# main_low_pass.net
KiCad netlist of a schematic drawn in EAGLE
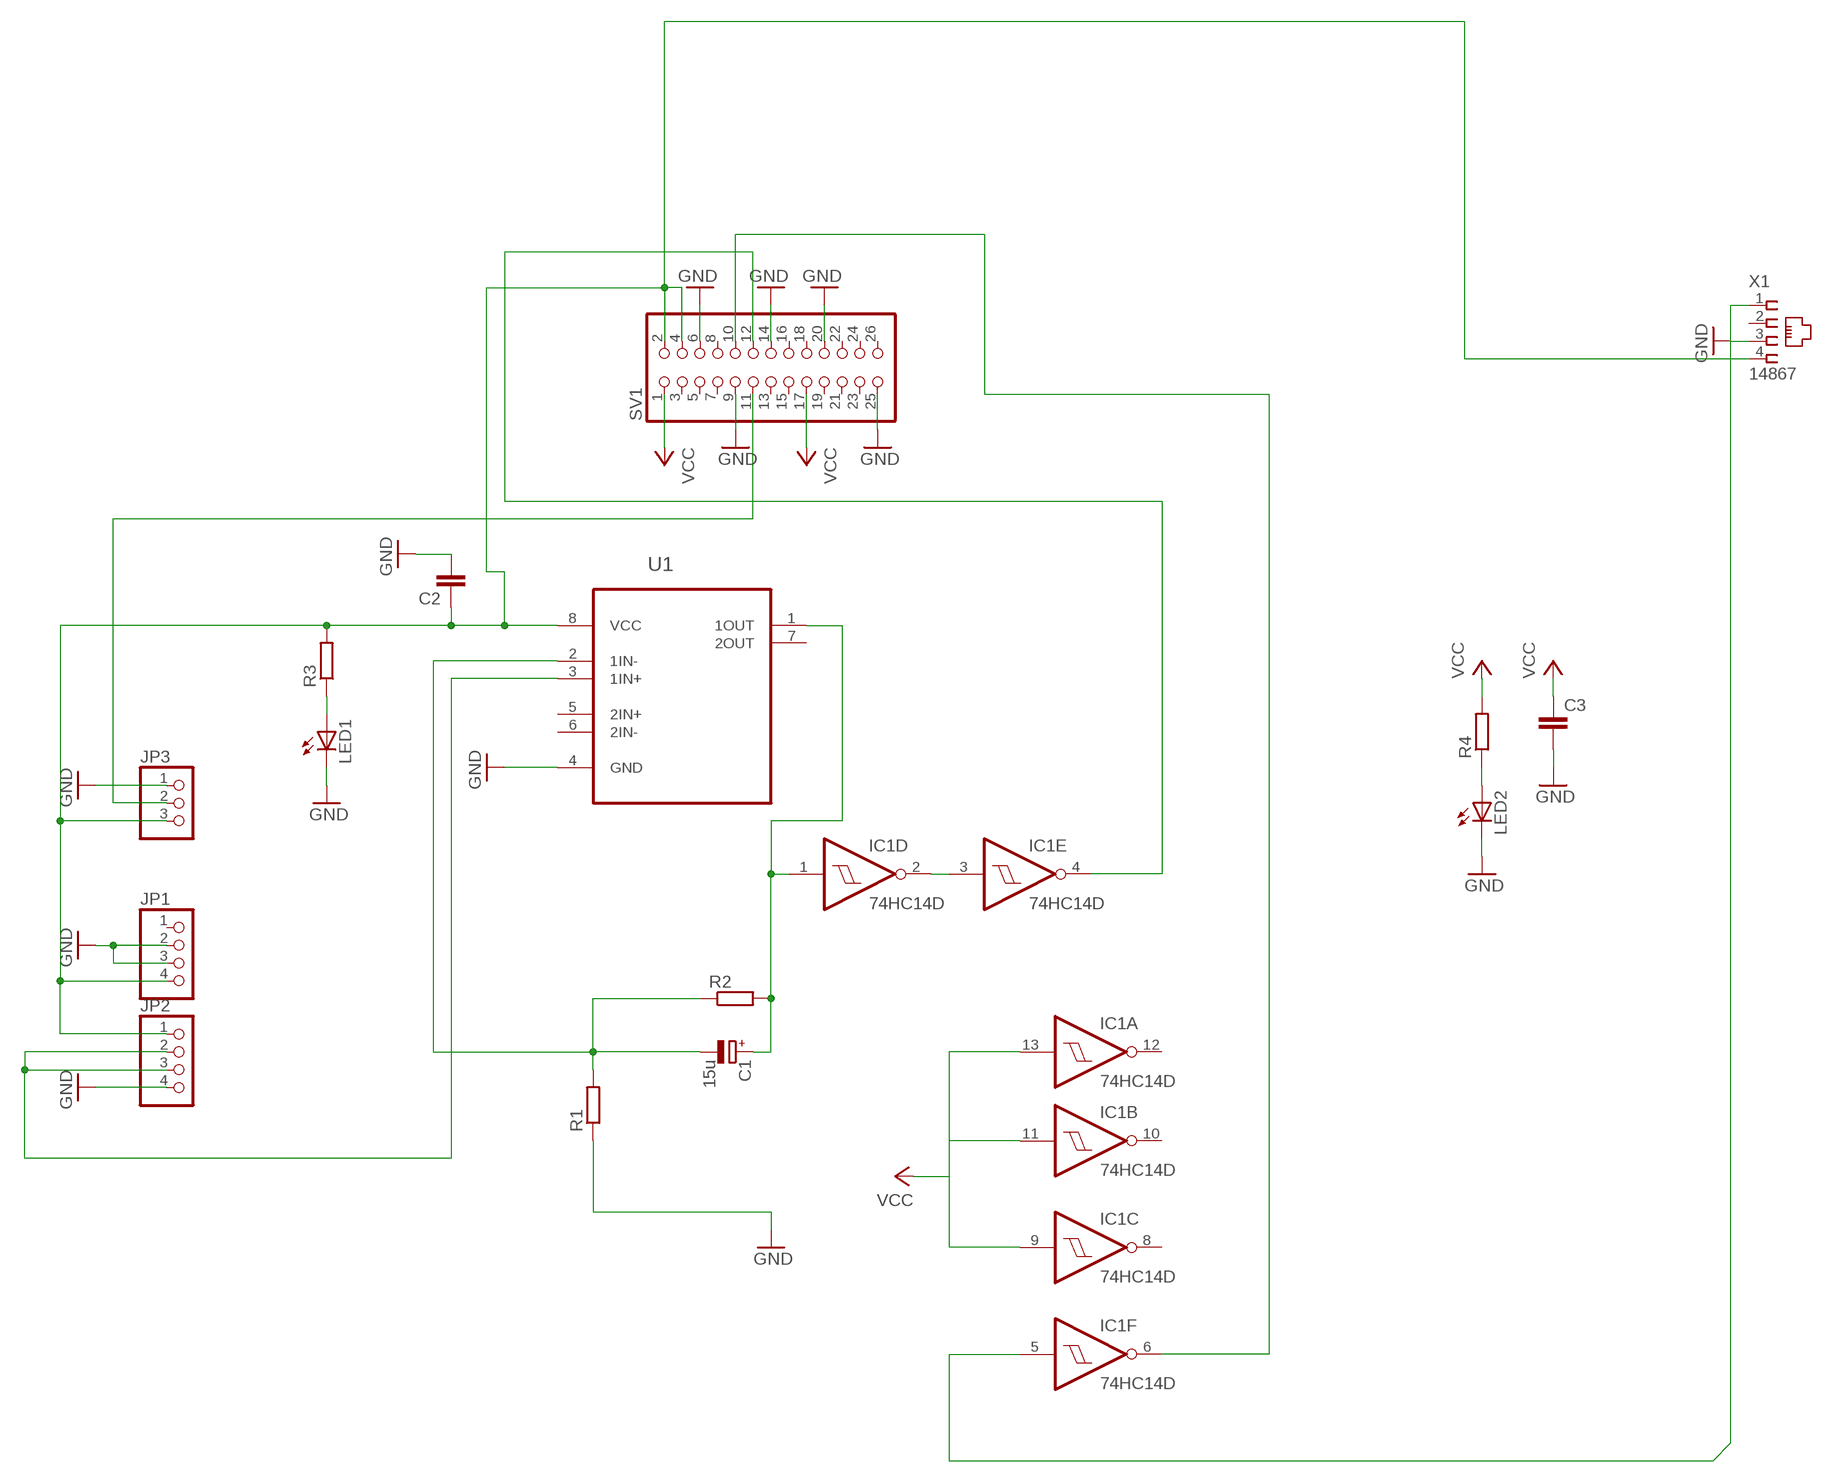
[diagram p0: schematic, sheet 1]

(export (version "E")
  (design (tool "Eeschema 10.0.6"))
  (components
    (comp (ref "C1")
      (value "15u")
      (footprint "eagle-import:153CLV-0605")
      (libsource (lib "eagle-import") (part "CPOL-EU153CLV-0605"))
    )
    (comp (ref "C2")
      (value "C-EUC0805")
      (footprint "eagle-import:C0805")
      (libsource (lib "eagle-import") (part "C-EUC0805"))
    )
    (comp (ref "C3")
      (value "C-EUC0805")
      (footprint "eagle-import:C0805")
      (libsource (lib "eagle-import") (part "C-EUC0805"))
    )
    (comp (ref "IC1")
      (value "74HC14D")
      (footprint "eagle-import:SO14")
      (libsource (lib "eagle-import") (part "7414DHC"))
    )
    (comp (ref "JP1")
      (value "PINHD-1X4")
      (footprint "eagle-import:1X04")
      (libsource (lib "eagle-import") (part "PINHD-1X4"))
    )
    (comp (ref "JP2")
      (value "PINHD-1X4")
      (footprint "eagle-import:1X04")
      (libsource (lib "eagle-import") (part "PINHD-1X4"))
    )
    (comp (ref "JP3")
      (value "PINHD-1X3")
      (footprint "eagle-import:1X03")
      (libsource (lib "eagle-import") (part "PINHD-1X3"))
    )
    (comp (ref "LED1")
      (value "LEDCHIP-LED0805")
      (footprint "eagle-import:CHIP-LED0805")
      (libsource (lib "eagle-import") (part "LEDCHIP-LED0805"))
    )
    (comp (ref "LED2")
      (value "LEDCHIP-LED0805")
      (footprint "eagle-import:CHIP-LED0805")
      (libsource (lib "eagle-import") (part "LEDCHIP-LED0805"))
    )
    (comp (ref "R1")
      (value "R-EU_R0805")
      (footprint "eagle-import:R0805")
      (libsource (lib "eagle-import") (part "R-EU_R0805"))
    )
    (comp (ref "R2")
      (value "R-EU_R0805")
      (footprint "eagle-import:R0805")
      (libsource (lib "eagle-import") (part "R-EU_R0805"))
    )
    (comp (ref "R3")
      (value "R-EU_R0805")
      (footprint "eagle-import:R0805")
      (libsource (lib "eagle-import") (part "R-EU_R0805"))
    )
    (comp (ref "R4")
      (value "R-EU_R0805")
      (footprint "eagle-import:R0805")
      (libsource (lib "eagle-import") (part "R-EU_R0805"))
    )
    (comp (ref "SV1")
      (value "PINHD-2X13")
      (footprint "eagle-import:2X13")
      (libsource (lib "eagle-import") (part "PINHD-2X13"))
    )
    (comp (ref "U1")
      (value "LM358PW")
      (footprint "eagle-import:SOP65P640X120-8N")
      (libsource (lib "eagle-import") (part "LM358PW"))
    )
    (comp (ref "X1")
      (value "14867")
      (footprint "eagle-import:14867")
      (libsource (lib "eagle-import") (part "14867"))
    )
  )
  (nets
    (net (code "1") (name "GND") (class "Default")
      (node (ref "C2") (pin "2") (pinfunction "2_2") (pintype "passive"))
      (node (ref "C3") (pin "2") (pinfunction "2_2") (pintype "passive"))
      (node (ref "JP1") (pin "2") (pinfunction "2_2") (pintype "passive"))
      (node (ref "JP1") (pin "3") (pinfunction "3_3") (pintype "passive"))
      (node (ref "JP2") (pin "4") (pinfunction "4_4") (pintype "passive"))
      (node (ref "JP3") (pin "1") (pinfunction "1_1") (pintype "passive"))
      (node (ref "LED1") (pin "C") (pinfunction "C_C") (pintype "passive"))
      (node (ref "LED2") (pin "C") (pinfunction "C_C") (pintype "passive"))
      (node (ref "R1") (pin "1") (pinfunction "1_1") (pintype "passive"))
      (node (ref "SV1") (pin "14") (pinfunction "14_14") (pintype "passive"))
      (node (ref "SV1") (pin "20") (pinfunction "20_20") (pintype "passive"))
      (node (ref "SV1") (pin "25") (pinfunction "25_25") (pintype "passive"))
      (node (ref "SV1") (pin "6") (pinfunction "6_6") (pintype "passive"))
      (node (ref "SV1") (pin "9") (pinfunction "9_9") (pintype "passive"))
      (node (ref "U1") (pin "4") (pinfunction "GND_4") (pintype "passive"))
      (node (ref "X1") (pin "3") (pinfunction "3_3") (pintype "passive"))
    )
    (net (code "2") (name "Net-(IC1D-I)") (class "Default")
      (node (ref "C1") (pin "+") (pinfunction "+_+") (pintype "passive"))
      (node (ref "IC1") (pin "1") (pinfunction "I_1") (pintype "input"))
      (node (ref "R2") (pin "2") (pinfunction "2_2") (pintype "passive"))
      (node (ref "U1") (pin "1") (pinfunction "1OUT_1") (pintype "output"))
    )
    (net (code "3") (name "Net-(IC1D-O)") (class "Default")
      (node (ref "IC1") (pin "2") (pinfunction "O_2") (pintype "output"))
      (node (ref "IC1") (pin "3") (pinfunction "I_3") (pintype "input"))
    )
    (net (code "4") (name "Net-(IC1E-O)") (class "Default")
      (node (ref "IC1") (pin "4") (pinfunction "O_4") (pintype "output"))
      (node (ref "SV1") (pin "12") (pinfunction "12_12") (pintype "passive"))
    )
    (net (code "5") (name "Net-(IC1F-I)") (class "Default")
      (node (ref "IC1") (pin "5") (pinfunction "I_5") (pintype "input"))
      (node (ref "X1") (pin "1") (pinfunction "1_1") (pintype "passive"))
    )
    (net (code "6") (name "Net-(IC1F-O)") (class "Default")
      (node (ref "IC1") (pin "6") (pinfunction "O_6") (pintype "output"))
      (node (ref "SV1") (pin "10") (pinfunction "10_10") (pintype "passive"))
    )
    (net (code "7") (name "Net-(JP3-Pad2)") (class "Default")
      (node (ref "JP3") (pin "2") (pinfunction "2_2") (pintype "passive"))
      (node (ref "SV1") (pin "11") (pinfunction "11_11") (pintype "passive"))
    )
    (net (code "8") (name "Net-(LED1-PadA)") (class "Default")
      (node (ref "LED1") (pin "A") (pinfunction "A_A") (pintype "passive"))
      (node (ref "R3") (pin "1") (pinfunction "1_1") (pintype "passive"))
    )
    (net (code "9") (name "Net-(LED2-PadA)") (class "Default")
      (node (ref "LED2") (pin "A") (pinfunction "A_A") (pintype "passive"))
      (node (ref "R4") (pin "1") (pinfunction "1_1") (pintype "passive"))
    )
    (net (code "10") (name "Net-(U1-1IN+)") (class "Default")
      (node (ref "JP2") (pin "2") (pinfunction "2_2") (pintype "passive"))
      (node (ref "JP2") (pin "3") (pinfunction "3_3") (pintype "passive"))
      (node (ref "U1") (pin "3") (pinfunction "1IN+_3") (pintype "input"))
    )
    (net (code "11") (name "Net-(U1-1IN-)") (class "Default")
      (node (ref "C1") (pin "-") (pinfunction "-_-") (pintype "passive"))
      (node (ref "R1") (pin "2") (pinfunction "2_2") (pintype "passive"))
      (node (ref "R2") (pin "1") (pinfunction "1_1") (pintype "passive"))
      (node (ref "U1") (pin "2") (pinfunction "1IN-_2") (pintype "input"))
    )
    (net (code "12") (name "Net-(U1-VCC)") (class "Default")
      (node (ref "C2") (pin "1") (pinfunction "1_1") (pintype "passive"))
      (node (ref "JP1") (pin "4") (pinfunction "4_4") (pintype "passive"))
      (node (ref "JP2") (pin "1") (pinfunction "1_1") (pintype "passive"))
      (node (ref "JP3") (pin "3") (pinfunction "3_3") (pintype "passive"))
      (node (ref "R3") (pin "2") (pinfunction "2_2") (pintype "passive"))
      (node (ref "SV1") (pin "2") (pinfunction "2_2") (pintype "passive"))
      (node (ref "SV1") (pin "4") (pinfunction "4_4") (pintype "passive"))
      (node (ref "U1") (pin "8") (pinfunction "VCC_8") (pintype "power_in"))
      (node (ref "X1") (pin "4") (pinfunction "4_4") (pintype "passive"))
    )
    (net (code "13") (name "VCC") (class "Default")
      (node (ref "C3") (pin "1") (pinfunction "1_1") (pintype "passive"))
      (node (ref "IC1") (pin "11") (pinfunction "I_11") (pintype "input"))
      (node (ref "IC1") (pin "13") (pinfunction "I_13") (pintype "input"))
      (node (ref "IC1") (pin "9") (pinfunction "I_9") (pintype "input"))
      (node (ref "R4") (pin "2") (pinfunction "2_2") (pintype "passive"))
      (node (ref "SV1") (pin "1") (pinfunction "1_1") (pintype "passive"))
      (node (ref "SV1") (pin "17") (pinfunction "17_17") (pintype "passive"))
    )
    (net (code "14") (name "unconnected-(IC1A-O-Pad12)") (class "Default")
      (node (ref "IC1") (pin "12") (pinfunction "O_12") (pintype "output"))
    )
    (net (code "15") (name "unconnected-(IC1B-O-Pad10)") (class "Default")
      (node (ref "IC1") (pin "10") (pinfunction "O_10") (pintype "output"))
    )
    (net (code "16") (name "unconnected-(IC1C-O-Pad8)") (class "Default")
      (node (ref "IC1") (pin "8") (pinfunction "O_8") (pintype "output"))
    )
    (net (code "17") (name "unconnected-(JP1-Pad1)") (class "Default")
      (node (ref "JP1") (pin "1") (pinfunction "1_1") (pintype "passive"))
    )
    (net (code "18") (name "unconnected-(SV1-Pad3)") (class "Default")
      (node (ref "SV1") (pin "3") (pinfunction "3_3") (pintype "passive"))
    )
    (net (code "19") (name "unconnected-(SV1-Pad5)") (class "Default")
      (node (ref "SV1") (pin "5") (pinfunction "5_5") (pintype "passive"))
    )
    (net (code "20") (name "unconnected-(SV1-Pad7)") (class "Default")
      (node (ref "SV1") (pin "7") (pinfunction "7_7") (pintype "passive"))
    )
    (net (code "21") (name "unconnected-(SV1-Pad8)") (class "Default")
      (node (ref "SV1") (pin "8") (pinfunction "8_8") (pintype "passive"))
    )
    (net (code "22") (name "unconnected-(SV1-Pad13)") (class "Default")
      (node (ref "SV1") (pin "13") (pinfunction "13_13") (pintype "passive"))
    )
    (net (code "23") (name "unconnected-(SV1-Pad15)") (class "Default")
      (node (ref "SV1") (pin "15") (pinfunction "15_15") (pintype "passive"))
    )
    (net (code "24") (name "unconnected-(SV1-Pad16)") (class "Default")
      (node (ref "SV1") (pin "16") (pinfunction "16_16") (pintype "passive"))
    )
    (net (code "25") (name "unconnected-(SV1-Pad18)") (class "Default")
      (node (ref "SV1") (pin "18") (pinfunction "18_18") (pintype "passive"))
    )
    (net (code "26") (name "unconnected-(SV1-Pad19)") (class "Default")
      (node (ref "SV1") (pin "19") (pinfunction "19_19") (pintype "passive"))
    )
    (net (code "27") (name "unconnected-(SV1-Pad21)") (class "Default")
      (node (ref "SV1") (pin "21") (pinfunction "21_21") (pintype "passive"))
    )
    (net (code "28") (name "unconnected-(SV1-Pad22)") (class "Default")
      (node (ref "SV1") (pin "22") (pinfunction "22_22") (pintype "passive"))
    )
    (net (code "29") (name "unconnected-(SV1-Pad23)") (class "Default")
      (node (ref "SV1") (pin "23") (pinfunction "23_23") (pintype "passive"))
    )
    (net (code "30") (name "unconnected-(SV1-Pad24)") (class "Default")
      (node (ref "SV1") (pin "24") (pinfunction "24_24") (pintype "passive"))
    )
    (net (code "31") (name "unconnected-(SV1-Pad26)") (class "Default")
      (node (ref "SV1") (pin "26") (pinfunction "26_26") (pintype "passive"))
    )
    (net (code "32") (name "unconnected-(U1-2IN+-Pad5)") (class "Default")
      (node (ref "U1") (pin "5") (pinfunction "2IN+_5") (pintype "input"))
    )
    (net (code "33") (name "unconnected-(U1-2IN--Pad6)") (class "Default")
      (node (ref "U1") (pin "6") (pinfunction "2IN-_6") (pintype "input"))
    )
    (net (code "34") (name "unconnected-(U1-2OUT-Pad7)") (class "Default")
      (node (ref "U1") (pin "7") (pinfunction "2OUT_7") (pintype "output"))
    )
    (net (code "35") (name "unconnected-(X1-Pad2)") (class "Default")
      (node (ref "X1") (pin "2") (pinfunction "2_2") (pintype "passive"))
    )
  )
)
